# tinyheader.net
KiCad netlist of a schematic drawn in EAGLE
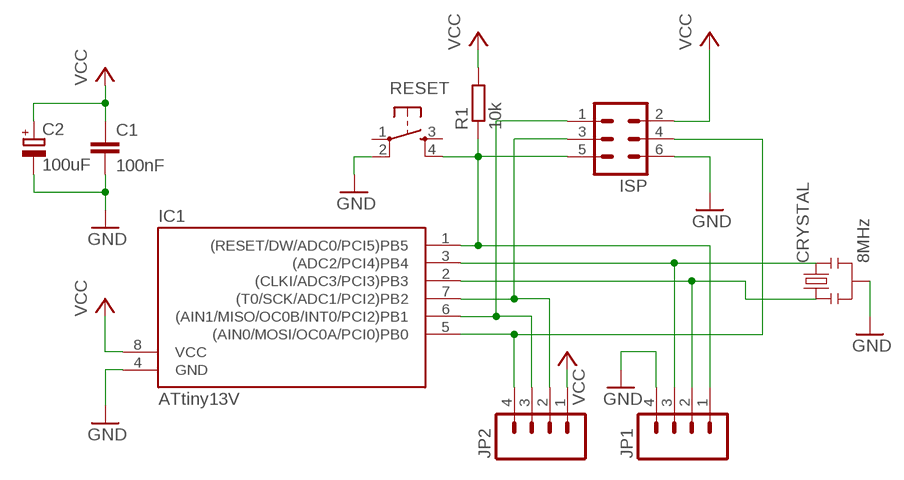
[diagram p0: schematic, sheet 1]

(export (version "E")
  (design (tool "Eeschema 10.0.6"))
  (components
    (comp (ref "C1")
      (value "100nF")
      (footprint "eagle-import:C025-025X050")
      (fields (field (name "MF") "VISHAY/SPRAGUE") (field (name "MPN") "1C20Z5U104M050B"))
      (libsource (lib "eagle-import") (part "C-EU025-025X050"))
    )
    (comp (ref "C2")
      (value "100uF")
      (footprint "eagle-import:E2,5-6E")
      (fields (field (name "MPN") "100YXF100MEFC12.5X20"))
      (libsource (lib "eagle-import") (part "CPOL-EUE2,5-6E"))
    )
    (comp (ref "CRYSTAL")
      (value "8MHz")
      (footprint "eagle-import:RESONATOR-PTH")
      (fields (field (name "MPN") "C8M000000L004"))
      (libsource (lib "eagle-import") (part "RESONATORPTH"))
    )
    (comp (ref "IC1")
      (value "ATtiny13V")
      (footprint "eagle-import:DIL08")
      (fields (field (name "MPN") "ATTINY13V-10PU"))
      (libsource (lib "eagle-import") (part "ATTINY13P-20"))
    )
    (comp (ref "ISP")
      (value "MA03-2")
      (footprint "eagle-import:MA03-2")
      (libsource (lib "eagle-import") (part "MA03-2"))
    )
    (comp (ref "JP1")
      (value "M04PTH")
      (footprint "eagle-import:1X04")
      (libsource (lib "eagle-import") (part "M04PTH"))
    )
    (comp (ref "JP2")
      (value "M04PTH")
      (footprint "eagle-import:1X04")
      (libsource (lib "eagle-import") (part "M04PTH"))
    )
    (comp (ref "R1")
      (value "10k")
      (footprint "eagle-import:0207_5V")
      (fields (field (name "MF") "FARNELL") (field (name "MPN") "MCF 0.5W 10K"))
      (libsource (lib "eagle-import") (part "R-EU_0207/5V"))
    )
    (comp (ref "RESET")
      (value "TAC_SWITCHSND")
      (footprint "eagle-import:TACTILE_SWITCH_SMD")
      (libsource (lib "eagle-import") (part "TAC_SWITCHSND"))
    )
  )
  (nets
    (net (code "1") (name "GND") (class "Default")
      (node (ref "C1") (pin "2") (pinfunction "2_2") (pintype "passive"))
      (node (ref "C2") (pin "-") (pinfunction "-_-") (pintype "passive"))
      (node (ref "CRYSTAL") (pin "2") (pinfunction "2_2") (pintype "passive"))
      (node (ref "IC1") (pin "4") (pinfunction "GND_4") (pintype "power_in"))
      (node (ref "ISP") (pin "6") (pinfunction "6_6") (pintype "passive"))
      (node (ref "JP1") (pin "4") (pinfunction "4_4") (pintype "passive"))
      (node (ref "RESET") (pin "2") (pinfunction "2_2") (pintype "passive"))
    )
    (net (code "2") (name "Net-(IC1-(ADC2{slash}PCI4)PB4)") (class "Default")
      (node (ref "CRYSTAL") (pin "3") (pinfunction "3_3") (pintype "passive"))
      (node (ref "IC1") (pin "3") (pinfunction "(ADC2/PCI4)PB4_3") (pintype "bidirectional"))
      (node (ref "JP1") (pin "3") (pinfunction "3_3") (pintype "passive"))
    )
    (net (code "3") (name "Net-(IC1-(AIN0{slash}MOSI{slash}OC0A{slash}PCI0)PB0)") (class "Default")
      (node (ref "IC1") (pin "5") (pinfunction "(AIN0/MOSI/OC0A/PCI0)PB0_5") (pintype "bidirectional"))
      (node (ref "ISP") (pin "4") (pinfunction "4_4") (pintype "passive"))
      (node (ref "JP2") (pin "4") (pinfunction "4_4") (pintype "passive"))
    )
    (net (code "4") (name "Net-(IC1-(AIN1{slash}MISO{slash}OC0B{slash}INT0{slash}PCI2)PB1)") (class "Default")
      (node (ref "IC1") (pin "6") (pinfunction "(AIN1/MISO/OC0B/INT0/PCI2)PB1_6") (pintype "bidirectional"))
      (node (ref "ISP") (pin "1") (pinfunction "1_1") (pintype "passive"))
      (node (ref "JP2") (pin "3") (pinfunction "3_3") (pintype "passive"))
    )
    (net (code "5") (name "Net-(IC1-(CLKI{slash}ADC3{slash}PCI3)PB3)") (class "Default")
      (node (ref "CRYSTAL") (pin "1") (pinfunction "1_1") (pintype "passive"))
      (node (ref "IC1") (pin "2") (pinfunction "(CLKI/ADC3/PCI3)PB3_2") (pintype "bidirectional"))
      (node (ref "JP1") (pin "2") (pinfunction "2_2") (pintype "passive"))
    )
    (net (code "6") (name "Net-(IC1-(RESET{slash}DW{slash}ADC0{slash}PCI5)PB5)") (class "Default")
      (node (ref "IC1") (pin "1") (pinfunction "(RESET/DW/ADC0/PCI5)PB5_1") (pintype "bidirectional"))
      (node (ref "ISP") (pin "5") (pinfunction "5_5") (pintype "passive"))
      (node (ref "JP1") (pin "1") (pinfunction "1_1") (pintype "passive"))
      (node (ref "R1") (pin "1") (pinfunction "1_1") (pintype "passive"))
      (node (ref "RESET") (pin "4") (pinfunction "4_4") (pintype "passive"))
    )
    (net (code "7") (name "Net-(IC1-(T0{slash}SCK{slash}ADC1{slash}PCI2)PB2)") (class "Default")
      (node (ref "IC1") (pin "7") (pinfunction "(T0/SCK/ADC1/PCI2)PB2_7") (pintype "bidirectional"))
      (node (ref "ISP") (pin "3") (pinfunction "3_3") (pintype "passive"))
      (node (ref "JP2") (pin "2") (pinfunction "2_2") (pintype "passive"))
    )
    (net (code "8") (name "VCC") (class "Default")
      (node (ref "C1") (pin "1") (pinfunction "1_1") (pintype "passive"))
      (node (ref "C2") (pin "+") (pinfunction "+_+") (pintype "passive"))
      (node (ref "IC1") (pin "8") (pinfunction "VCC_8") (pintype "power_in"))
      (node (ref "ISP") (pin "2") (pinfunction "2_2") (pintype "passive"))
      (node (ref "JP2") (pin "1") (pinfunction "1_1") (pintype "passive"))
      (node (ref "R1") (pin "2") (pinfunction "2_2") (pintype "passive"))
    )
    (net (code "9") (name "unconnected-(RESET-Pad1)") (class "Default")
      (node (ref "RESET") (pin "1") (pinfunction "1_1") (pintype "passive"))
    )
    (net (code "10") (name "unconnected-(RESET-Pad3)") (class "Default")
      (node (ref "RESET") (pin "3") (pinfunction "3_3") (pintype "passive"))
    )
  )
)
